# supply_unit.net
KiCad netlist of a schematic drawn in Altium Designer
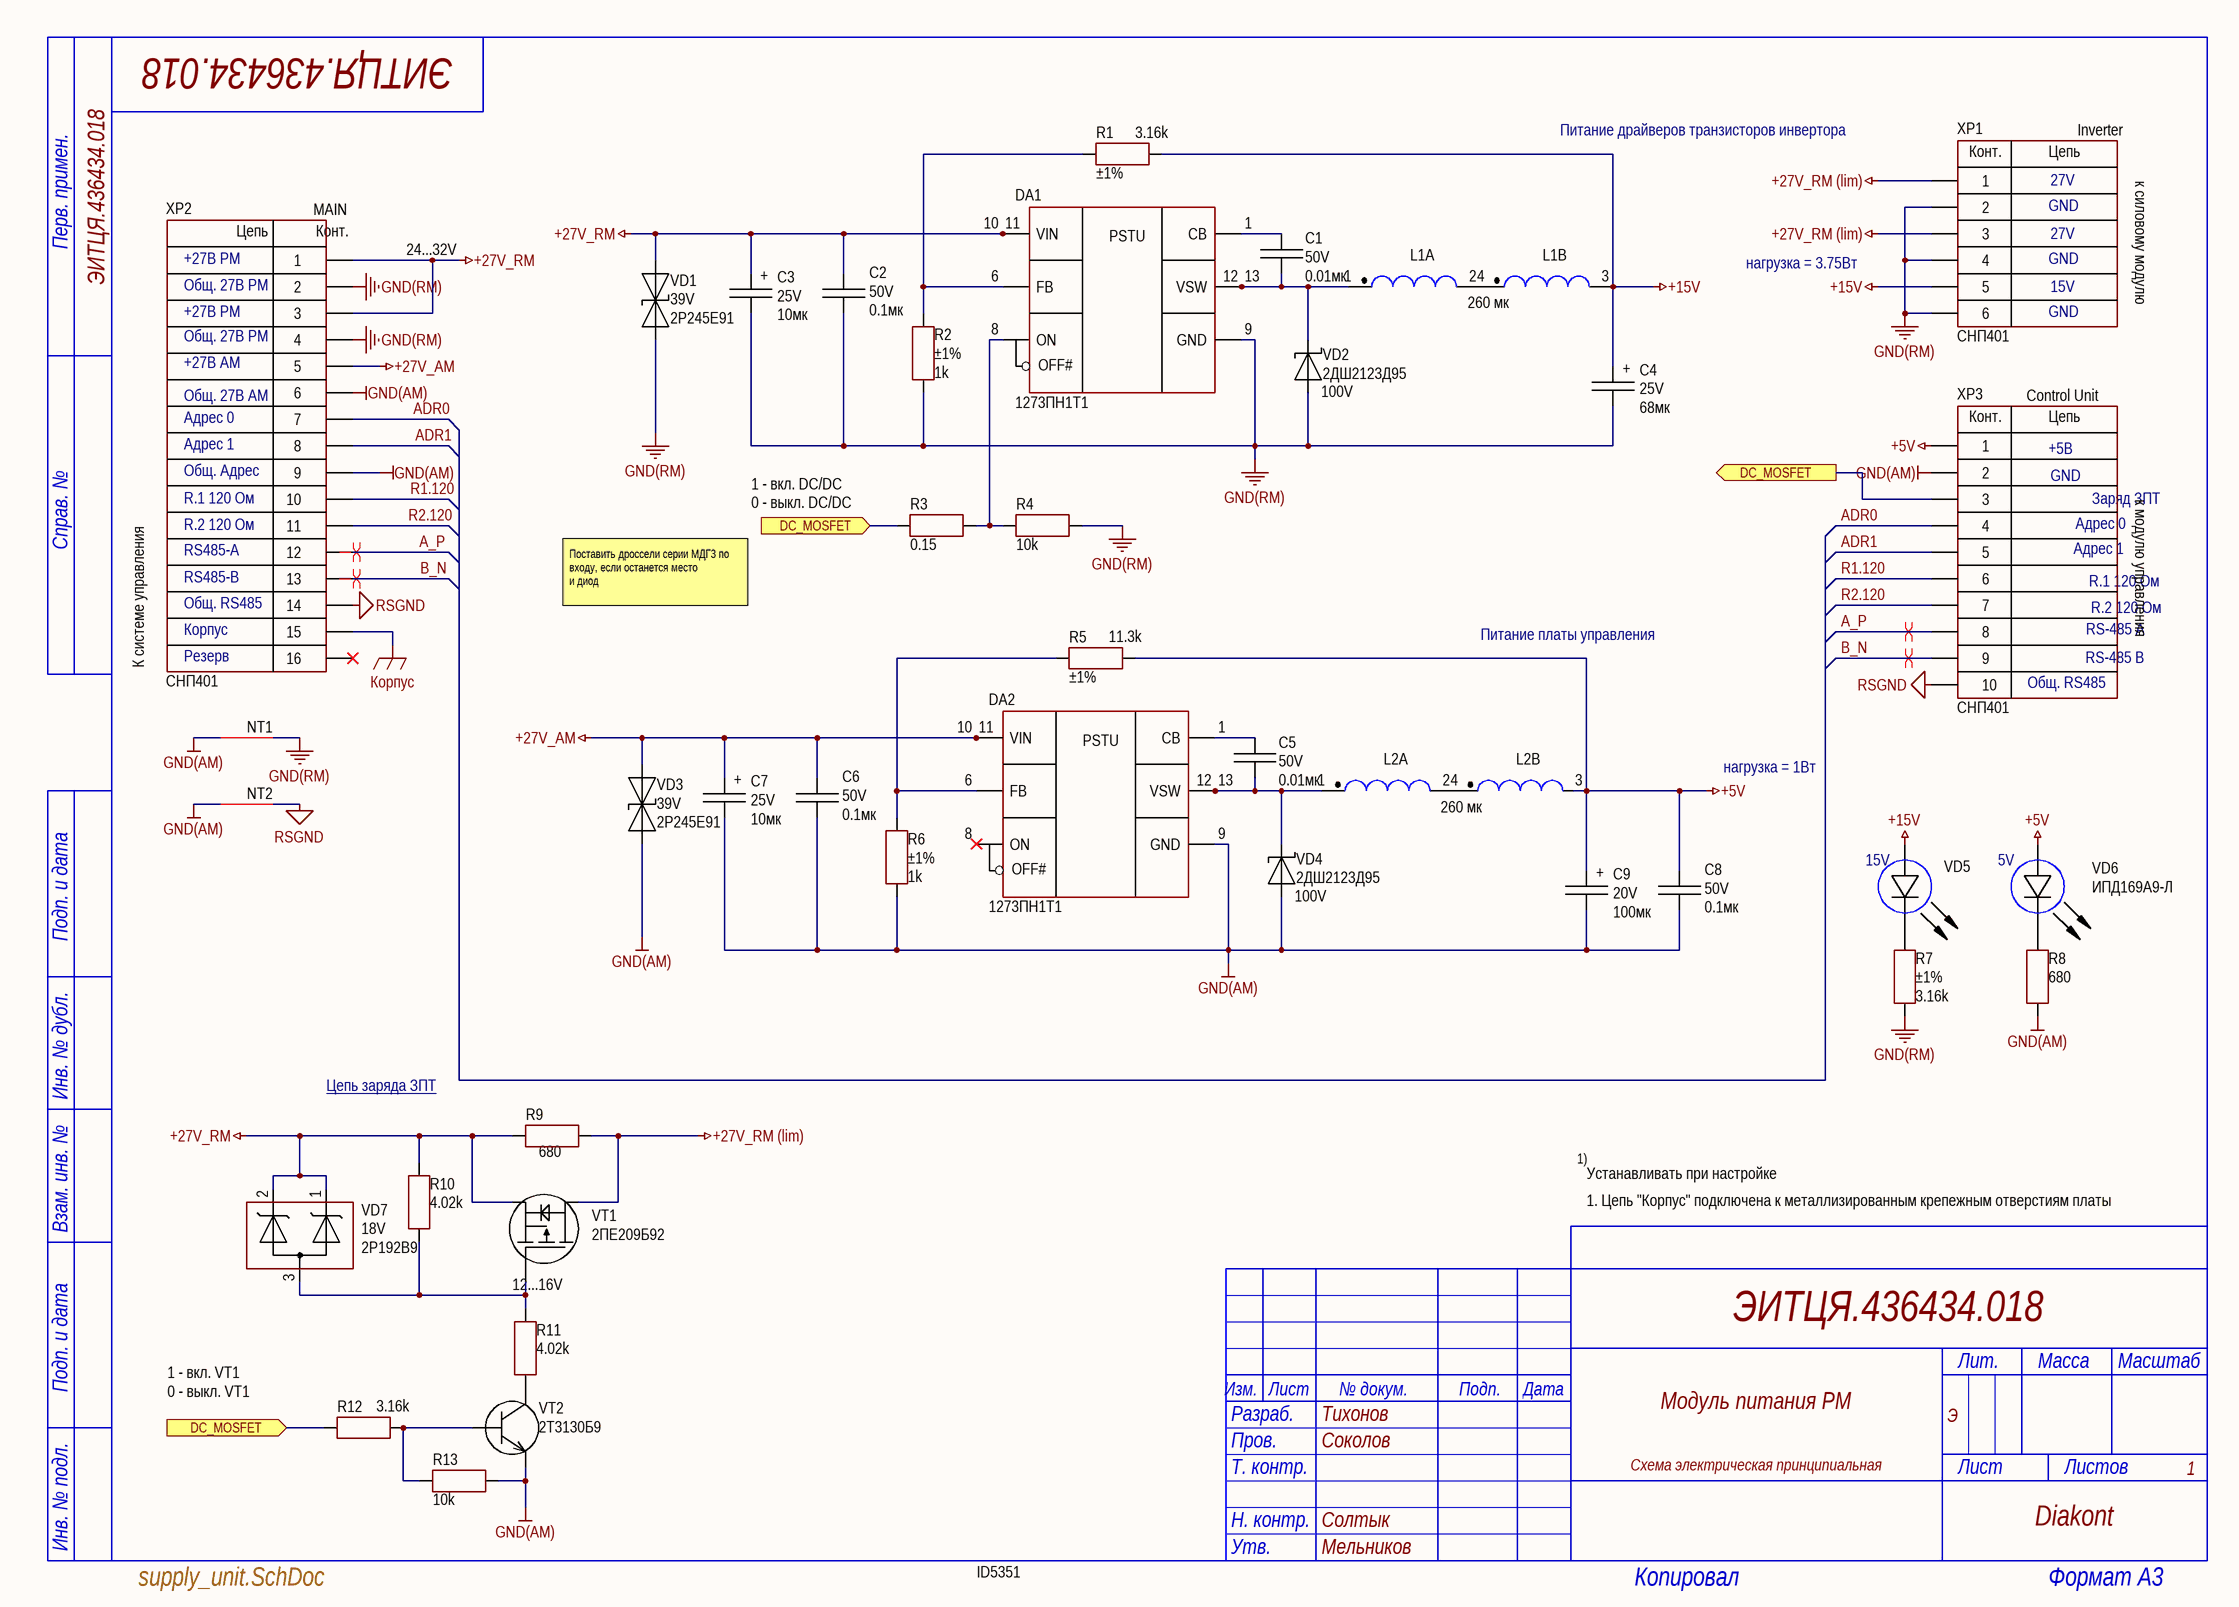
[diagram p0: supply_unit.SchDoc]

(export (version "E")
  (design (tool "Eeschema 10.0.6"))
  (components
    (comp (ref "C1")
      (value "0.01мк")
      (footprint "StandardCase:CAP: 0603+0805")
      (fields
        (field (name "MANUFACTURER") "Монолит")
        (field (name "PARTNUMBER") "К10-84в-1608М-50В-0,01 мкФ ±10%-Н20-N-A")
        (field (name "VALUEMANUFACTURERPARTNUMBER") "Ceramic capacitor, 0.01мк, Н20, ±10%, 50V, 0603, ")
        (field (name "VOLTAGE") "50V")
      )
      (libsource (lib "Capacitor") (part "Ceramic_0603"))
    )
    (comp (ref "C2")
      (value "0.1мк")
      (footprint "StandardCase:CAP: 0805+1206")
      (fields
        (field (name "MANUFACTURER") "Монолит")
        (field (name "PARTNUMBER") "К10-84в-2012М-50В-0,1 мкФ +80/-20%-Н90-N-A")
        (field (name "VALUEMANUFACTURERPARTNUMBER") "Ceramic capacitor, 0.1мк, Н20, ±10%, 50V, 0805, ")
        (field (name "VOLTAGE") "50V")
      )
      (libsource (lib "Capacitor") (part "Ceramic_1210"))
    )
    (comp (ref "C3")
      (value "10мк")
      (footprint "StandardCase:CAP: TANTAL-E")
      (fields
        (field (name "MANUFACTURER") "Элеконд")
        (field (name "PARTNUMBER") "К53-68 \"E\"-50 В-10мкф ±10%")
        (field (name "VALUEMANUFACTURERPARTNUMBER") "Tantalum capacitor, 10мк, 25V, ±10%, 0.7 Ом, case E, -60...+125°C")
        (field (name "POLARITY") "+")
        (field (name "VOLTAGE") "25V")
      )
      (libsource (lib "Capacitor") (part "Tantal_E"))
    )
    (comp (ref "C4")
      (value "68мк")
      (footprint "StandardCase:CAP: TANTAL-E")
      (fields
        (field (name "MANUFACTURER") "Элеконд")
        (field (name "PARTNUMBER") "К53-68 \"E\"-25 В-68мкф ±10%")
        (field (name "VALUEMANUFACTURERPARTNUMBER") "Tantalum capacitor, 68мк, 25V, ±10%, 0.7 Ом, case E, -60...+125°C")
        (field (name "POLARITY") "+")
        (field (name "VOLTAGE") "25V")
      )
      (libsource (lib "Capacitor") (part "Tantal_E"))
    )
    (comp (ref "C5")
      (value "0.01мк")
      (footprint "StandardCase:CAP: 0603+0805")
      (fields
        (field (name "MANUFACTURER") "Монолит")
        (field (name "PARTNUMBER") "К10-84в-1608М-50В-0,01 мкФ ±10%-Н20-N-A")
        (field (name "VALUEMANUFACTURERPARTNUMBER") "Ceramic capacitor, 0.01мк, Н20, ±10%, 50V, 0603, ")
        (field (name "VOLTAGE") "50V")
      )
      (libsource (lib "Capacitor") (part "Ceramic_0603"))
    )
    (comp (ref "C6")
      (value "0.1мк")
      (footprint "StandardCase:CAP: 0805+1206")
      (fields
        (field (name "MANUFACTURER") "Монолит")
        (field (name "PARTNUMBER") "К10-84в-2012М-50В-0,1 мкФ +80/-20%-Н90-N-A")
        (field (name "VALUEMANUFACTURERPARTNUMBER") "Ceramic capacitor, 0.1мк, Н20, ±10%, 50V, 0805, ")
        (field (name "VOLTAGE") "50V")
      )
      (libsource (lib "Capacitor") (part "Ceramic_1210"))
    )
    (comp (ref "C7")
      (value "10мк")
      (footprint "StandardCase:CAP: TANTAL-E")
      (fields
        (field (name "MANUFACTURER") "Элеконд")
        (field (name "PARTNUMBER") "К53-68 \"E\"-50 В-10мкф ±10%")
        (field (name "VALUEMANUFACTURERPARTNUMBER") "Tantalum capacitor, 10мк, 25V, ±10%, 0.7 Ом, case E, -60...+125°C")
        (field (name "POLARITY") "+")
        (field (name "VOLTAGE") "25V")
      )
      (libsource (lib "Capacitor") (part "Tantal_E"))
    )
    (comp (ref "C8")
      (value "0.1мк")
      (footprint "StandardCase:CAP: 0805+1206")
      (fields
        (field (name "MANUFACTURER") "Монолит")
        (field (name "PARTNUMBER") "К10-84в-2012М-50В-0,1 мкФ +80/-20%-Н90-N-A")
        (field (name "VALUEMANUFACTURERPARTNUMBER") "Ceramic capacitor, 0.1мк, Н20, ±10%, 50V, 0805, ")
        (field (name "VOLTAGE") "50V")
      )
      (libsource (lib "Capacitor") (part "Ceramic_1210"))
    )
    (comp (ref "C9")
      (value "100мк")
      (footprint "StandardCase:CAP: TANTAL-E")
      (fields
        (field (name "MANUFACTURER") "Элеконд")
        (field (name "PARTNUMBER") "К53-68 \"E\"-20 В-100 мкф ±10%")
        (field (name "VALUEMANUFACTURERPARTNUMBER") "Tantalum capacitor, 100мк, 20V, ±10%, 0.5-0.7 Ом, case E, -60...+125°C")
        (field (name "POLARITY") "+")
        (field (name "VOLTAGE") "20V")
      )
      (libsource (lib "Capacitor") (part "Tantal_E"))
    )
    (comp (ref "DA1")
      (value "~")
      (footprint "401.14-5М")
      (description "USSR Buck converter")
      (fields
        (field (name "MANUFACTURER") "НИИЭТ")
        (field (name "VALUEMANUFACTURERPARTNUMBER") "DC/DC buck converter, input 8...40V, 260 кHz, output 1.21...37V, 1A, -60...+115°C, 401.14-5М")
        (field (name "PARTNUMBER") "1273ПН1T1")
      )
      (libsource (lib "IC. Power supply") (part "1273ПН1T1"))
    )
    (comp (ref "DA2")
      (value "~")
      (footprint "401.14-5М")
      (description "USSR Buck converter")
      (fields
        (field (name "MANUFACTURER") "НИИЭТ")
        (field (name "VALUEMANUFACTURERPARTNUMBER") "DC/DC buck converter, input 8...40V, 260 кHz, output 1.21...37V, 1A, -60...+115°C, 401.14-5М")
        (field (name "PARTNUMBER") "1273ПН1T1")
      )
      (libsource (lib "IC. Power supply") (part "1273ПН1T1"))
    )
    (comp (ref "L1")
      (value "260 мк")
      (footprint "IND: DFPK7_5")
      (description "Дроссель фильтрации")
      (fields (field (name "MANUFACTURER") "АЛЕКСАНДЕР ЭЛЕКТРИК") (field (name "PARTNUMBER") "ДФПК7,5-2/0.8"))
      (libsource (lib "Inductor") (part "ДФПК7,5-2/x"))
    )
    (comp (ref "L2")
      (value "260 мк")
      (footprint "IND: DFPK7_5")
      (description "Дроссель фильтрации")
      (fields (field (name "MANUFACTURER") "АЛЕКСАНДЕР ЭЛЕКТРИК") (field (name "PARTNUMBER") "ДФПК7,5-2/0.8"))
      (libsource (lib "Inductor") (part "ДФПК7,5-2/x"))
    )
    (comp (ref "NT1")
      (value "~")
      (footprint "CustomCase:NetTie_0603")
      (libsource (lib "Connector") (part "NetTie"))
    )
    (comp (ref "NT2")
      (value "~")
      (footprint "CustomCase:NetTie_0603")
      (libsource (lib "Connector") (part "NetTie"))
    )
    (comp (ref "R1")
      (value "3.16k")
      (footprint "RES: 0603P")
      (fields
        (field (name "MANUFACTURER") "ОАО Ресурс")
        (field (name "PARTNUMBER") "Р1-12-0,1ум.-3.16~кОм ±1%-М ШКАБ.434110.002 ТУ")
        (field (name "VALUEMANUFACTURERPARTNUMBER") "Resistor film, 3.16k, ±1%, 0603, 0.1W, -55...+125°C")
        (field (name "TOLERANCE") "±1%")
      )
      (libsource (lib "") (part "Resistor_0603_2"))
    )
    (comp (ref "R2")
      (value "1k")
      (footprint "RES: 0603P")
      (fields
        (field (name "MANUFACTURER") "ОАО Ресурс")
        (field (name "PARTNUMBER") "Р1-12-0,1ум.-1~кОм ±1%-М ШКАБ.434110.002 ТУ")
        (field (name "VALUEMANUFACTURERPARTNUMBER") "Resistor film, 1k, ±1%, 0603, 0.1W, -55...+125°C")
        (field (name "TOLERANCE") "±1%")
      )
      (libsource (lib "Resistor") (part "Resistor_0603"))
    )
    (comp (ref "R3")
      (value "0.15")
      (footprint "RES: 0603P")
      (fields
        (field (name "MANUFACTURER") "ОАО Ресурс")
        (field (name "PARTNUMBER") "Р1-12-0,1ум.-0.15~Ом ±20%-М ШКАБ.434110.002 ТУ")
        (field (name "VALUEMANUFACTURERPARTNUMBER") "Resistor film, 0.15, ±20%, 0603, 0.1W, -55...+125°C")
      )
      (libsource (lib "") (part "Resistor_0603_2"))
    )
    (comp (ref "R4")
      (value "10k")
      (footprint "RES: 0603P")
      (fields
        (field (name "MANUFACTURER") "ОАО Ресурс")
        (field (name "PARTNUMBER") "Р1-12-0,1ум.-10~кОм ±5%-М ШКАБ.434110.002 ТУ")
        (field (name "VALUEMANUFACTURERPARTNUMBER") "Resistor film, 10k, ±5%, 0603, 0.1W, -55...+125°C")
      )
      (libsource (lib "Resistor") (part "Resistor_0603"))
    )
    (comp (ref "R5")
      (value "11.3k")
      (footprint "RES: 0603P")
      (fields
        (field (name "MANUFACTURER") "ОАО Ресурс")
        (field (name "PARTNUMBER") "Р1-12-0,1ум.-11.3~кОм ±1%-М ШКАБ.434110.002 ТУ")
        (field (name "VALUEMANUFACTURERPARTNUMBER") "Resistor film, 11.3k, ±1%, 0603, 0.1W, -55...+125°C")
        (field (name "TOLERANCE") "±1%")
      )
      (libsource (lib "") (part "Resistor_0603_2"))
    )
    (comp (ref "R6")
      (value "1k")
      (footprint "RES: 0603P")
      (fields
        (field (name "MANUFACTURER") "ОАО Ресурс")
        (field (name "PARTNUMBER") "Р1-12-0,1ум.-1~кОм ±1%-М ШКАБ.434110.002 ТУ")
        (field (name "VALUEMANUFACTURERPARTNUMBER") "Resistor film, 1k, ±1%, 0603, 0.1W, -55...+125°C")
        (field (name "TOLERANCE") "±1%")
      )
      (libsource (lib "Resistor") (part "Resistor_0603"))
    )
    (comp (ref "R7")
      (value "3.16k")
      (footprint "RES: 0603P")
      (fields
        (field (name "MANUFACTURER") "ОАО Ресурс")
        (field (name "PARTNUMBER") "Р1-12-0,1ум.-3.16~кОм ±1%-М ШКАБ.434110.002 ТУ")
        (field (name "VALUEMANUFACTURERPARTNUMBER") "Resistor film, 3.16k, ±1%, 0603, 0.1W, -55...+125°C")
        (field (name "TOLERANCE") "±1%")
      )
      (libsource (lib "") (part "Resistor_0603_3"))
    )
    (comp (ref "R8")
      (value "680")
      (footprint "RES: 0603P")
      (fields
        (field (name "MANUFACTURER") "ОАО Ресурс")
        (field (name "PARTNUMBER") "Р1-12-0,1ум.-680~Ом ±5%-М ШКАБ.434110.002 ТУ")
        (field (name "VALUEMANUFACTURERPARTNUMBER") "Resistor film, 680, ±5%, 0603, 0.1W, -55...+125°C")
      )
      (libsource (lib "") (part "Resistor_0603_1"))
    )
    (comp (ref "R9")
      (value "680")
      (footprint "StandardCase:RES: 0805P")
      (fields
        (field (name "MANUFACTURER") "Ресурс")
        (field (name "PARTNUMBER") "Р1-12-0,125-680 Ом ±5%-М ШКАБ.434110.002 ТУ")
        (field (name "VALUEMANUFACTURERPARTNUMBER") "Resistor film, 680, ±5%, 0805, 0.125W, ")
      )
      (libsource (lib "Resistor") (part "Resistor_0805"))
    )
    (comp (ref "R10")
      (value "4.02k")
      (fields
        (field (name "MANUFACTURER") "ОАО Ресурс")
        (field (name "PARTNUMBER") "Р1-12-0,1ум.-4.02~кОм ±1%-М ШКАБ.434110.002 ТУ")
        (field (name "VALUEMANUFACTURERPARTNUMBER") "Resistor film, 4.02k, ±1%, 0805, 0.125W, -55...+125°C")
      )
      (libsource (lib "") (part "Resistor_0603_1"))
    )
    (comp (ref "R11")
      (value "4.02k")
      (fields
        (field (name "MANUFACTURER") "ОАО Ресурс")
        (field (name "PARTNUMBER") "Р1-12-0,1ум.-4.02~кОм ±1%-М ШКАБ.434110.002 ТУ")
        (field (name "VALUEMANUFACTURERPARTNUMBER") "Resistor film, 4.02k, ±1%, 0805, 0.125W, -55...+125°C")
      )
      (libsource (lib "") (part "Resistor_0603_1"))
    )
    (comp (ref "R12")
      (value "3.16k")
      (footprint "RES: 0603P")
      (fields
        (field (name "MANUFACTURER") "ОАО Ресурс")
        (field (name "PARTNUMBER") "Р1-12-0,1ум.-3.16~кОм ±1%-М ШКАБ.434110.002 ТУ")
        (field (name "VALUEMANUFACTURERPARTNUMBER") "Resistor film, 3.16k, ±1%, 0603, 0.1W, -55...+125°C")
      )
      (libsource (lib "") (part "Resistor_0603_2"))
    )
    (comp (ref "R13")
      (value "10k")
      (footprint "RES: 0603P")
      (fields
        (field (name "MANUFACTURER") "ОАО Ресурс")
        (field (name "PARTNUMBER") "Р1-12-0,1ум.-10~кОм ±5%-М ШКАБ.434110.002 ТУ")
        (field (name "VALUEMANUFACTURERPARTNUMBER") "Resistor film, 10k, ±5%, 0603, 0.1W, -55...+125°C")
      )
      (libsource (lib "Resistor") (part "Resistor_0603"))
    )
    (comp (ref "VD1")
      (value "~")
      (footprint "StandardCase:DIODE: SMB")
      (fields
        (field (name "MANUFACTURER") "НЗПП")
        (field (name "VALUEMANUFACTURERPARTNUMBER") "Zener diode, 39V, 8A, 0.9V, , SMB(КД-42), ")
        (field (name "VOLTAGE") "39V")
        (field (name "PARTNUMBER") "2Р245Е91")
      )
      (libsource (lib "Diode") (part "TVS_single"))
    )
    (comp (ref "VD2")
      (value "ВЗПП Сборка Воронеж")
      (footprint "КТ-99-1")
      (fields (field (name "VOLTAGE") "100V") (field (name "PARTNUMBER") "2ДШ2123Д95"))
      (libsource (lib "Diode") (part "Schottky_single"))
    )
    (comp (ref "VD3")
      (value "~")
      (footprint "StandardCase:DIODE: SMB")
      (fields
        (field (name "MANUFACTURER") "НЗПП")
        (field (name "VALUEMANUFACTURERPARTNUMBER") "Zener diode, 39V, 8A, 0.9V, , SMB(КД-42), ")
        (field (name "VOLTAGE") "39V")
        (field (name "PARTNUMBER") "2Р245Е91")
      )
      (libsource (lib "Diode") (part "TVS_single"))
    )
    (comp (ref "VD4")
      (value "ВЗПП Сборка Воронеж")
      (footprint "КТ-99-1")
      (fields (field (name "VOLTAGE") "100V") (field (name "PARTNUMBER") "2ДШ2123Д95"))
      (libsource (lib "Diode") (part "Schottky_single"))
    )
    (comp (ref "VD5")
      (value "~")
      (footprint "StandardCase:LED: 0603G")
      (fields
        (field (name "MANUFACTURER") "Протон")
        (field (name "VALUEMANUFACTURERPARTNUMBER") "LED, 20mA max, 2.1V typ, 1608, -55...+150°C")
        (field (name "PARTNUMBER") "ИПД169А9-Л")
        (field (name "COMMENTTEXT") "15V")
      )
      (libsource (lib "Diode") (part "LED_single"))
    )
    (comp (ref "VD6")
      (value "~")
      (footprint "StandardCase:LED: 0603G")
      (fields
        (field (name "MANUFACTURER") "Протон")
        (field (name "VALUEMANUFACTURERPARTNUMBER") "LED, 20mA max, 2.1V typ, 1608, -55...+150°C")
        (field (name "PARTNUMBER") "ИПД169А9-Л")
        (field (name "COMMENTTEXT") "5V")
      )
      (libsource (lib "Diode") (part "LED_single"))
    )
    (comp (ref "VD7")
      (value "~")
      (footprint "StandardCase:SOT23")
      (fields
        (field (name "MANUFACTURER") "КРИП")
        (field (name "VALUEMANUFACTURERPARTNUMBER") "TVS diode, 18V, 1A, , , SOT-23, -55...+150°C")
        (field (name "VOLTAGE") "18V")
        (field (name "PARTNUMBER") "2Р192В9")
      )
      (libsource (lib "Diode") (part "TVS_array_var2"))
    )
    (comp (ref "VT1")
      (value "~")
      (footprint "StandardCase:DPAK")
      (fields (field (name "MANUFACTURER") "Ангстрем") (field (name "PARTNUMBER") "2ПЕ209Б92"))
      (libsource (lib "Transistor") (part "MOSFET_P_132"))
    )
    (comp (ref "VT2")
      (value "~")
      (footprint "SOT23")
      (fields
        (field (name "MANUFACTURER") "ООО НПК Далекс")
        (field (name "VALUEMANUFACTURERPARTNUMBER") "NPN transistor, 30V, 100mA, , 300mW, 0.7V, 500, SOT-23 (КТ-46), -55...+125°C")
        (field (name "PARTNUMBER") "2Т3130Б9")
      )
      (libsource (lib "Transistor") (part "BJT_NPN_132"))
    )
    (comp (ref "XP1")
      (value "~")
      (footprint "CON: M80-5000605")
      (description "вилка на плату")
      (fields
        (field (name "MANUFACTURER") "Электроделать")
        (field (name "VALUEMANUFACTURERPARTNUMBER") "Вилка, 6pin, 2mm, 120VAC, 1.5A")
        (field (name "COMMENTTEXT") "СНП401")
      )
      (libsource (lib "Connector") (part "M80-5000605 Harwin"))
    )
    (comp (ref "XP2")
      (value "~")
      (footprint "CustomCase:CON: M80-5001605")
      (description "вилка на плату")
      (fields
        (field (name "MANUFACTURER") "Электродеталь")
        (field (name "VALUEMANUFACTURERPARTNUMBER") ", 16pin, 2mm, 120VAC, 1.5A")
        (field (name "COMMENTTEXT") "СНП401")
      )
      (libsource (lib "Connector") (part "M80-5001205 Harwin_1"))
    )
    (comp (ref "XP3")
      (value "~")
      (footprint "CON: HR M80-500S10")
      (description "вилка на плату")
      (fields
        (field (name "MANUFACTURER") "Электродеталь")
        (field (name "VALUEMANUFACTURERPARTNUMBER") "Вилка, 10pin, 2mm, 100V, 1.5A")
        (field (name "COMMENTTEXT") "СНП401")
      )
      (libsource (lib "Connector") (part "M80-5001005 Harwin"))
    )
  )
  (nets
    (net (code "1") (name "+5V") (class "Default")
      (node (ref "C8") (pin "2") (pinfunction "2_2") (pintype "passive"))
      (node (ref "C9") (pin "2") (pinfunction "2_2") (pintype "power_in"))
      (node (ref "L2") (pin "3") (pinfunction "3_3") (pintype "passive"))
      (node (ref "R5") (pin "2") (pinfunction "2_2") (pintype "passive"))
      (node (ref "VD6") (pin "1") (pinfunction "A_1") (pintype "passive"))
      (node (ref "XP3") (pin "1") (pinfunction "1_1") (pintype "passive"))
    )
    (net (code "2") (name "+15V") (class "Default")
      (node (ref "C4") (pin "2") (pinfunction "2_2") (pintype "power_in"))
      (node (ref "L1") (pin "3") (pinfunction "3_3") (pintype "passive"))
      (node (ref "R1") (pin "2") (pinfunction "2_2") (pintype "passive"))
      (node (ref "VD5") (pin "1") (pinfunction "A_1") (pintype "passive"))
      (node (ref "XP1") (pin "5") (pinfunction "5_5") (pintype "passive"))
    )
    (net (code "3") (name "+27V_AM") (class "Default")
      (node (ref "C6") (pin "2") (pinfunction "2_2") (pintype "passive"))
      (node (ref "C7") (pin "2") (pinfunction "2_2") (pintype "power_in"))
      (node (ref "DA2") (pin "10") (pinfunction "VIN_10") (pintype "passive"))
      (node (ref "DA2") (pin "11") (pinfunction "VIN_11") (pintype "passive"))
      (node (ref "VD3") (pin "2") (pinfunction "C_2") (pintype "passive"))
      (node (ref "XP2") (pin "5") (pinfunction "5_5") (pintype "passive"))
    )
    (net (code "4") (name "+27V_RM") (class "Default")
      (node (ref "C2") (pin "2") (pinfunction "2_2") (pintype "passive"))
      (node (ref "C3") (pin "2") (pinfunction "2_2") (pintype "power_in"))
      (node (ref "DA1") (pin "10") (pinfunction "VIN_10") (pintype "passive"))
      (node (ref "DA1") (pin "11") (pinfunction "VIN_11") (pintype "passive"))
      (node (ref "R10") (pin "1") (pinfunction "1_1") (pintype "passive"))
      (node (ref "R9") (pin "1") (pinfunction "1_1") (pintype "passive"))
      (node (ref "VD1") (pin "2") (pinfunction "C_2") (pintype "passive"))
      (node (ref "VD7") (pin "1") (pinfunction "K1_1") (pintype "passive"))
      (node (ref "VD7") (pin "2") (pinfunction "K2_2") (pintype "passive"))
      (node (ref "VT1") (pin "2") (pinfunction "S_2") (pintype "passive"))
      (node (ref "XP2") (pin "1") (pinfunction "1_1") (pintype "passive"))
      (node (ref "XP2") (pin "3") (pinfunction "3_3") (pintype "passive"))
    )
    (net (code "5") (name "+27V_RM (lim)") (class "Default")
      (node (ref "R9") (pin "2") (pinfunction "2_2") (pintype "passive"))
      (node (ref "VT1") (pin "3") (pinfunction "D_3") (pintype "passive"))
      (node (ref "XP1") (pin "1") (pinfunction "1_1") (pintype "passive"))
      (node (ref "XP1") (pin "3") (pinfunction "3_3") (pintype "passive"))
    )
    (net (code "6") (name "/ADR0") (class "Default")
      (node (ref "XP2") (pin "7") (pinfunction "7_7") (pintype "passive"))
      (node (ref "XP3") (pin "4") (pinfunction "4_4") (pintype "passive"))
    )
    (net (code "7") (name "/ADR1") (class "Default")
      (node (ref "XP2") (pin "8") (pinfunction "8_8") (pintype "passive"))
      (node (ref "XP3") (pin "5") (pinfunction "5_5") (pintype "passive"))
    )
    (net (code "8") (name "/A_P") (class "Default")
      (node (ref "XP2") (pin "12") (pinfunction "12_12") (pintype "passive"))
      (node (ref "XP3") (pin "8") (pinfunction "8_8") (pintype "passive"))
    )
    (net (code "9") (name "/B_N") (class "Default")
      (node (ref "XP2") (pin "13") (pinfunction "13_13") (pintype "passive"))
      (node (ref "XP3") (pin "9") (pinfunction "9_9") (pintype "passive"))
    )
    (net (code "10") (name "/DC_MOSFET") (class "Default")
      (node (ref "R12") (pin "1") (pinfunction "1_1") (pintype "passive"))
      (node (ref "R3") (pin "1") (pinfunction "1_1") (pintype "passive"))
      (node (ref "XP3") (pin "3") (pinfunction "3_3") (pintype "passive"))
    )
    (net (code "11") (name "/R1.120") (class "Default")
      (node (ref "XP2") (pin "10") (pinfunction "10_10") (pintype "passive"))
      (node (ref "XP3") (pin "6") (pinfunction "6_6") (pintype "passive"))
    )
    (net (code "12") (name "/R2.120") (class "Default")
      (node (ref "XP2") (pin "11") (pinfunction "11_11") (pintype "passive"))
      (node (ref "XP3") (pin "7") (pinfunction "7_7") (pintype "passive"))
    )
    (net (code "13") (name "GND(AM)") (class "Default")
      (node (ref "C6") (pin "1") (pinfunction "1_1") (pintype "passive"))
      (node (ref "C7") (pin "1") (pinfunction "1_1") (pintype "power_in"))
      (node (ref "C8") (pin "1") (pinfunction "1_1") (pintype "passive"))
      (node (ref "C9") (pin "1") (pinfunction "1_1") (pintype "power_in"))
      (node (ref "DA2") (pin "9") (pinfunction "GND_9") (pintype "passive"))
      (node (ref "NT1") (pin "1") (pinfunction "1_1") (pintype "passive"))
      (node (ref "NT2") (pin "1") (pinfunction "1_1") (pintype "passive"))
      (node (ref "R13") (pin "1") (pinfunction "1_1") (pintype "passive"))
      (node (ref "R6") (pin "2") (pinfunction "2_2") (pintype "passive"))
      (node (ref "R8") (pin "2") (pinfunction "2_2") (pintype "passive"))
      (node (ref "VD3") (pin "1") (pinfunction "A_1") (pintype "passive"))
      (node (ref "VD4") (pin "A") (pinfunction "A_A") (pintype "passive"))
      (node (ref "VT2") (pin "2") (pinfunction "E_2") (pintype "passive"))
      (node (ref "XP2") (pin "6") (pinfunction "6_6") (pintype "passive"))
      (node (ref "XP2") (pin "9") (pinfunction "9_9") (pintype "passive"))
      (node (ref "XP3") (pin "2") (pinfunction "2_2") (pintype "passive"))
    )
    (net (code "14") (name "GND(RM)") (class "Default")
      (node (ref "C2") (pin "1") (pinfunction "1_1") (pintype "passive"))
      (node (ref "C3") (pin "1") (pinfunction "1_1") (pintype "power_in"))
      (node (ref "C4") (pin "1") (pinfunction "1_1") (pintype "power_in"))
      (node (ref "DA1") (pin "9") (pinfunction "GND_9") (pintype "passive"))
      (node (ref "NT1") (pin "2") (pinfunction "2_2") (pintype "passive"))
      (node (ref "R2") (pin "2") (pinfunction "2_2") (pintype "passive"))
      (node (ref "R4") (pin "1") (pinfunction "1_1") (pintype "passive"))
      (node (ref "R7") (pin "1") (pinfunction "1_1") (pintype "passive"))
      (node (ref "VD1") (pin "1") (pinfunction "A_1") (pintype "passive"))
      (node (ref "VD2") (pin "A") (pinfunction "A_A") (pintype "passive"))
      (node (ref "XP1") (pin "2") (pinfunction "2_2") (pintype "passive"))
      (node (ref "XP1") (pin "4") (pinfunction "4_4") (pintype "passive"))
      (node (ref "XP1") (pin "6") (pinfunction "6_6") (pintype "passive"))
      (node (ref "XP2") (pin "2") (pinfunction "2_2") (pintype "passive"))
      (node (ref "XP2") (pin "4") (pinfunction "4_4") (pintype "passive"))
    )
    (net (code "15") (name "Net-(C1-Pad1)") (class "Default")
      (node (ref "C1") (pin "1") (pinfunction "1_1") (pintype "passive"))
      (node (ref "DA1") (pin "12") (pinfunction "VSW_12") (pintype "passive"))
      (node (ref "DA1") (pin "13") (pinfunction "VSW_13") (pintype "passive"))
      (node (ref "L1") (pin "1") (pinfunction "1_1") (pintype "passive"))
      (node (ref "VD2") (pin "C") (pinfunction "C_C") (pintype "passive"))
    )
    (net (code "16") (name "Net-(C5-Pad1)") (class "Default")
      (node (ref "C5") (pin "1") (pinfunction "1_1") (pintype "passive"))
      (node (ref "DA2") (pin "12") (pinfunction "VSW_12") (pintype "passive"))
      (node (ref "DA2") (pin "13") (pinfunction "VSW_13") (pintype "passive"))
      (node (ref "L2") (pin "1") (pinfunction "1_1") (pintype "passive"))
      (node (ref "VD4") (pin "C") (pinfunction "C_C") (pintype "passive"))
    )
    (net (code "17") (name "Net-(DA1-CB)") (class "Default")
      (node (ref "C1") (pin "2") (pinfunction "2_2") (pintype "passive"))
      (node (ref "DA1") (pin "1") (pinfunction "CB_1") (pintype "passive"))
    )
    (net (code "18") (name "Net-(DA1-FB)") (class "Default")
      (node (ref "DA1") (pin "6") (pinfunction "FB_6") (pintype "passive"))
      (node (ref "R1") (pin "1") (pinfunction "1_1") (pintype "passive"))
      (node (ref "R2") (pin "1") (pinfunction "1_1") (pintype "passive"))
    )
    (net (code "19") (name "Net-(DA1-ON)") (class "Default")
      (node (ref "DA1") (pin "8") (pinfunction "ON_8") (pintype "passive"))
      (node (ref "R3") (pin "2") (pinfunction "2_2") (pintype "passive"))
      (node (ref "R4") (pin "2") (pinfunction "2_2") (pintype "passive"))
    )
    (net (code "20") (name "Net-(DA2-CB)") (class "Default")
      (node (ref "C5") (pin "2") (pinfunction "2_2") (pintype "passive"))
      (node (ref "DA2") (pin "1") (pinfunction "CB_1") (pintype "passive"))
    )
    (net (code "21") (name "Net-(DA2-FB)") (class "Default")
      (node (ref "DA2") (pin "6") (pinfunction "FB_6") (pintype "passive"))
      (node (ref "R5") (pin "1") (pinfunction "1_1") (pintype "passive"))
      (node (ref "R6") (pin "1") (pinfunction "1_1") (pintype "passive"))
    )
    (net (code "22") (name "Net-(L1-Pad2)") (class "Default")
      (node (ref "L1") (pin "2") (pinfunction "2_2") (pintype "passive"))
      (node (ref "L1") (pin "4") (pinfunction "4_4") (pintype "passive"))
    )
    (net (code "23") (name "Net-(L2-Pad2)") (class "Default")
      (node (ref "L2") (pin "2") (pinfunction "2_2") (pintype "passive"))
      (node (ref "L2") (pin "4") (pinfunction "4_4") (pintype "passive"))
    )
    (net (code "24") (name "Net-(VD5-C)") (class "Default")
      (node (ref "R7") (pin "2") (pinfunction "2_2") (pintype "passive"))
      (node (ref "VD5") (pin "2") (pinfunction "C_2") (pintype "passive"))
    )
    (net (code "25") (name "Net-(VD6-C)") (class "Default")
      (node (ref "R8") (pin "1") (pinfunction "1_1") (pintype "passive"))
      (node (ref "VD6") (pin "2") (pinfunction "C_2") (pintype "passive"))
    )
    (net (code "26") (name "Net-(VD7-A)") (class "Default")
      (node (ref "R10") (pin "2") (pinfunction "2_2") (pintype "passive"))
      (node (ref "R11") (pin "1") (pinfunction "1_1") (pintype "passive"))
      (node (ref "VD7") (pin "3") (pinfunction "A_3") (pintype "passive"))
      (node (ref "VT1") (pin "1") (pinfunction "G_1") (pintype "passive"))
    )
    (net (code "27") (name "Net-(VT2-B)") (class "Default")
      (node (ref "R12") (pin "2") (pinfunction "2_2") (pintype "passive"))
      (node (ref "R13") (pin "2") (pinfunction "2_2") (pintype "passive"))
      (node (ref "VT2") (pin "1") (pinfunction "B_1") (pintype "passive"))
    )
    (net (code "28") (name "Net-(VT2-C)") (class "Default")
      (node (ref "R11") (pin "2") (pinfunction "2_2") (pintype "passive"))
      (node (ref "VT2") (pin "3") (pinfunction "C_3") (pintype "passive"))
    )
    (net (code "29") (name "RSGND") (class "Default")
      (node (ref "NT2") (pin "2") (pinfunction "2_2") (pintype "passive"))
      (node (ref "XP2") (pin "14") (pinfunction "14_14") (pintype "passive"))
      (node (ref "XP3") (pin "10") (pinfunction "10_10") (pintype "passive"))
    )
    (net (code "30") (name "unconnected-(DA2-ON-Pad8)") (class "Default")
      (node (ref "DA2") (pin "8") (pinfunction "ON_8") (pintype "passive+no_connect"))
    )
    (net (code "31") (name "unconnected-(XP2-Pad16)") (class "Default")
      (node (ref "XP2") (pin "16") (pinfunction "16_16") (pintype "passive+no_connect"))
    )
    (net (code "32") (name "Корпус") (class "Default")
      (node (ref "XP2") (pin "15") (pinfunction "15_15") (pintype "passive"))
    )
  )
)
